# LSGTB.net
KiCad netlist of a schematic drawn in EAGLE
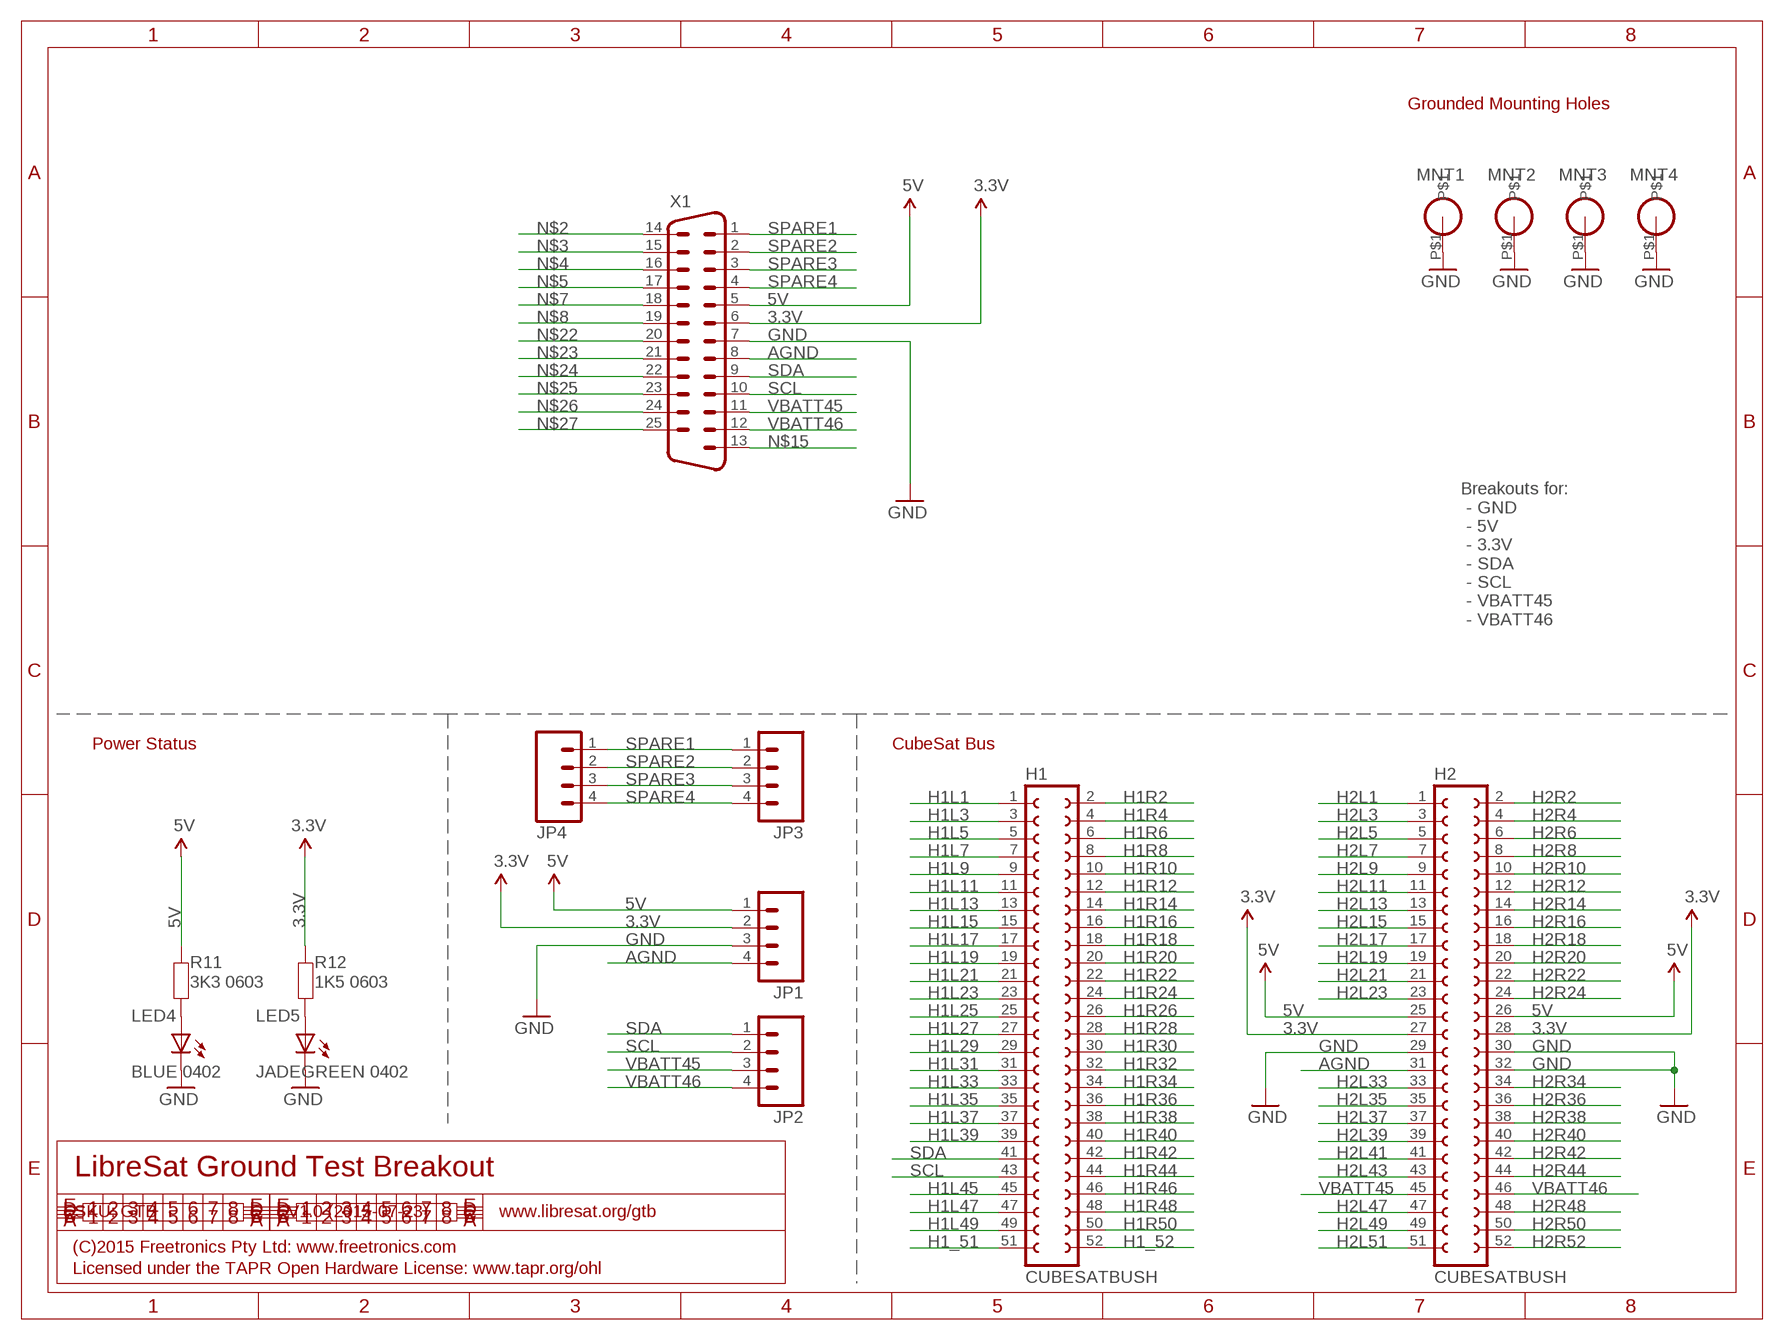
[diagram p0: schematic, sheet 1]

(export (version "E")
  (design (tool "Eeschema 10.0.6"))
  (components
    (comp (ref "H1")
      (value "CUBESATBUSH")
      (footprint "eagle-import:CUBESATBUS")
      (libsource (lib "eagle-import") (part "CUBESATBUSH"))
    )
    (comp (ref "H2")
      (value "CUBESATBUSH")
      (footprint "eagle-import:CUBESATBUS")
      (libsource (lib "eagle-import") (part "CUBESATBUSH"))
    )
    (comp (ref "JP1")
      (value "M04SCREW")
      (footprint "eagle-import:SCREWTERMINAL-3.5MM-4")
      (libsource (lib "eagle-import") (part "M04SCREW"))
    )
    (comp (ref "JP2")
      (value "M04SCREW")
      (footprint "eagle-import:SCREWTERMINAL-3.5MM-4")
      (libsource (lib "eagle-import") (part "M04SCREW"))
    )
    (comp (ref "JP3")
      (value "M04SCREW")
      (footprint "eagle-import:SCREWTERMINAL-3.5MM-4")
      (libsource (lib "eagle-import") (part "M04SCREW"))
    )
    (comp (ref "JP4")
      (value "M04PTH")
      (footprint "eagle-import:1X04")
      (libsource (lib "eagle-import") (part "M04PTH"))
    )
    (comp (ref "LED4")
      (value "BLUE 0402")
      (footprint "eagle-import:LED-0603")
      (libsource (lib "eagle-import") (part "LED0603"))
    )
    (comp (ref "LED5")
      (value "JADEGREEN 0402")
      (footprint "eagle-import:LED-0603")
      (libsource (lib "eagle-import") (part "LED0603"))
    )
    (comp (ref "MNT1")
      (value "HOLE3.2MM")
      (footprint "eagle-import:HOLE32")
      (libsource (lib "eagle-import") (part "HOLE3.2MM"))
    )
    (comp (ref "MNT2")
      (value "HOLE3.2MM")
      (footprint "eagle-import:HOLE32")
      (libsource (lib "eagle-import") (part "HOLE3.2MM"))
    )
    (comp (ref "MNT3")
      (value "HOLE3.2MM")
      (footprint "eagle-import:HOLE32")
      (libsource (lib "eagle-import") (part "HOLE3.2MM"))
    )
    (comp (ref "MNT4")
      (value "HOLE3.2MM")
      (footprint "eagle-import:HOLE32")
      (libsource (lib "eagle-import") (part "HOLE3.2MM"))
    )
    (comp (ref "R11")
      (value "3K3 0603")
      (footprint "eagle-import:0603")
      (libsource (lib "eagle-import") (part "RESISTOR0603"))
    )
    (comp (ref "R12")
      (value "1K5 0603")
      (footprint "eagle-import:0603")
      (libsource (lib "eagle-import") (part "RESISTOR0603"))
    )
    (comp (ref "X1")
      (value "DB25HP")
      (footprint "eagle-import:M25HP")
      (libsource (lib "eagle-import") (part "DB25HP"))
    )
  )
  (nets
    (net (code "1") (name "/AGND") (class "Default")
      (node (ref "H2") (pin "31") (pinfunction "31_31") (pintype "passive"))
      (node (ref "JP1") (pin "4") (pinfunction "4_4") (pintype "passive"))
      (node (ref "X1") (pin "8") (pinfunction "8_8") (pintype "passive"))
    )
    (net (code "2") (name "/H1L1") (class "Default")
      (node (ref "H1") (pin "1") (pinfunction "1_1") (pintype "passive"))
    )
    (net (code "3") (name "/H1L3") (class "Default")
      (node (ref "H1") (pin "3") (pinfunction "3_3") (pintype "passive"))
    )
    (net (code "4") (name "/H1L5") (class "Default")
      (node (ref "H1") (pin "5") (pinfunction "5_5") (pintype "passive"))
    )
    (net (code "5") (name "/H1L7") (class "Default")
      (node (ref "H1") (pin "7") (pinfunction "7_7") (pintype "passive"))
    )
    (net (code "6") (name "/H1L9") (class "Default")
      (node (ref "H1") (pin "9") (pinfunction "9_9") (pintype "passive"))
    )
    (net (code "7") (name "/H1L11") (class "Default")
      (node (ref "H1") (pin "11") (pinfunction "11_11") (pintype "passive"))
    )
    (net (code "8") (name "/H1L13") (class "Default")
      (node (ref "H1") (pin "13") (pinfunction "13_13") (pintype "passive"))
    )
    (net (code "9") (name "/H1L15") (class "Default")
      (node (ref "H1") (pin "15") (pinfunction "15_15") (pintype "passive"))
    )
    (net (code "10") (name "/H1L17") (class "Default")
      (node (ref "H1") (pin "17") (pinfunction "17_17") (pintype "passive"))
    )
    (net (code "11") (name "/H1L19") (class "Default")
      (node (ref "H1") (pin "19") (pinfunction "19_19") (pintype "passive"))
    )
    (net (code "12") (name "/H1L21") (class "Default")
      (node (ref "H1") (pin "21") (pinfunction "21_21") (pintype "passive"))
    )
    (net (code "13") (name "/H1L23") (class "Default")
      (node (ref "H1") (pin "23") (pinfunction "23_23") (pintype "passive"))
    )
    (net (code "14") (name "/H1L25") (class "Default")
      (node (ref "H1") (pin "25") (pinfunction "25_25") (pintype "passive"))
    )
    (net (code "15") (name "/H1L27") (class "Default")
      (node (ref "H1") (pin "27") (pinfunction "27_27") (pintype "passive"))
    )
    (net (code "16") (name "/H1L29") (class "Default")
      (node (ref "H1") (pin "29") (pinfunction "29_29") (pintype "passive"))
    )
    (net (code "17") (name "/H1L31") (class "Default")
      (node (ref "H1") (pin "31") (pinfunction "31_31") (pintype "passive"))
    )
    (net (code "18") (name "/H1L33") (class "Default")
      (node (ref "H1") (pin "33") (pinfunction "33_33") (pintype "passive"))
    )
    (net (code "19") (name "/H1L35") (class "Default")
      (node (ref "H1") (pin "35") (pinfunction "35_35") (pintype "passive"))
    )
    (net (code "20") (name "/H1L37") (class "Default")
      (node (ref "H1") (pin "37") (pinfunction "37_37") (pintype "passive"))
    )
    (net (code "21") (name "/H1L39") (class "Default")
      (node (ref "H1") (pin "39") (pinfunction "39_39") (pintype "passive"))
    )
    (net (code "22") (name "/H1L45") (class "Default")
      (node (ref "H1") (pin "45") (pinfunction "45_45") (pintype "passive"))
    )
    (net (code "23") (name "/H1L47") (class "Default")
      (node (ref "H1") (pin "47") (pinfunction "47_47") (pintype "passive"))
    )
    (net (code "24") (name "/H1L49") (class "Default")
      (node (ref "H1") (pin "49") (pinfunction "49_49") (pintype "passive"))
    )
    (net (code "25") (name "/H1R2") (class "Default")
      (node (ref "H1") (pin "2") (pinfunction "2_2") (pintype "passive"))
    )
    (net (code "26") (name "/H1R4") (class "Default")
      (node (ref "H1") (pin "4") (pinfunction "4_4") (pintype "passive"))
    )
    (net (code "27") (name "/H1R6") (class "Default")
      (node (ref "H1") (pin "6") (pinfunction "6_6") (pintype "passive"))
    )
    (net (code "28") (name "/H1R8") (class "Default")
      (node (ref "H1") (pin "8") (pinfunction "8_8") (pintype "passive"))
    )
    (net (code "29") (name "/H1R10") (class "Default")
      (node (ref "H1") (pin "10") (pinfunction "10_10") (pintype "passive"))
    )
    (net (code "30") (name "/H1R12") (class "Default")
      (node (ref "H1") (pin "12") (pinfunction "12_12") (pintype "passive"))
    )
    (net (code "31") (name "/H1R14") (class "Default")
      (node (ref "H1") (pin "14") (pinfunction "14_14") (pintype "passive"))
    )
    (net (code "32") (name "/H1R16") (class "Default")
      (node (ref "H1") (pin "16") (pinfunction "16_16") (pintype "passive"))
    )
    (net (code "33") (name "/H1R18") (class "Default")
      (node (ref "H1") (pin "18") (pinfunction "18_18") (pintype "passive"))
    )
    (net (code "34") (name "/H1R20") (class "Default")
      (node (ref "H1") (pin "20") (pinfunction "20_20") (pintype "passive"))
    )
    (net (code "35") (name "/H1R22") (class "Default")
      (node (ref "H1") (pin "22") (pinfunction "22_22") (pintype "passive"))
    )
    (net (code "36") (name "/H1R24") (class "Default")
      (node (ref "H1") (pin "24") (pinfunction "24_24") (pintype "passive"))
    )
    (net (code "37") (name "/H1R26") (class "Default")
      (node (ref "H1") (pin "26") (pinfunction "26_26") (pintype "passive"))
    )
    (net (code "38") (name "/H1R28") (class "Default")
      (node (ref "H1") (pin "28") (pinfunction "28_28") (pintype "passive"))
    )
    (net (code "39") (name "/H1R30") (class "Default")
      (node (ref "H1") (pin "30") (pinfunction "30_30") (pintype "passive"))
    )
    (net (code "40") (name "/H1R32") (class "Default")
      (node (ref "H1") (pin "32") (pinfunction "32_32") (pintype "passive"))
    )
    (net (code "41") (name "/H1R34") (class "Default")
      (node (ref "H1") (pin "34") (pinfunction "34_34") (pintype "passive"))
    )
    (net (code "42") (name "/H1R36") (class "Default")
      (node (ref "H1") (pin "36") (pinfunction "36_36") (pintype "passive"))
    )
    (net (code "43") (name "/H1R38") (class "Default")
      (node (ref "H1") (pin "38") (pinfunction "38_38") (pintype "passive"))
    )
    (net (code "44") (name "/H1R40") (class "Default")
      (node (ref "H1") (pin "40") (pinfunction "40_40") (pintype "passive"))
    )
    (net (code "45") (name "/H1R42") (class "Default")
      (node (ref "H1") (pin "42") (pinfunction "42_42") (pintype "passive"))
    )
    (net (code "46") (name "/H1R44") (class "Default")
      (node (ref "H1") (pin "44") (pinfunction "44_44") (pintype "passive"))
    )
    (net (code "47") (name "/H1R46") (class "Default")
      (node (ref "H1") (pin "46") (pinfunction "46_46") (pintype "passive"))
    )
    (net (code "48") (name "/H1R48") (class "Default")
      (node (ref "H1") (pin "48") (pinfunction "48_48") (pintype "passive"))
    )
    (net (code "49") (name "/H1R50") (class "Default")
      (node (ref "H1") (pin "50") (pinfunction "50_50") (pintype "passive"))
    )
    (net (code "50") (name "/H1_51") (class "Default")
      (node (ref "H1") (pin "51") (pinfunction "51_51") (pintype "passive"))
    )
    (net (code "51") (name "/H1_52") (class "Default")
      (node (ref "H1") (pin "52") (pinfunction "52_52") (pintype "passive"))
    )
    (net (code "52") (name "/H2L1") (class "Default")
      (node (ref "H2") (pin "1") (pinfunction "1_1") (pintype "passive"))
    )
    (net (code "53") (name "/H2L3") (class "Default")
      (node (ref "H2") (pin "3") (pinfunction "3_3") (pintype "passive"))
    )
    (net (code "54") (name "/H2L5") (class "Default")
      (node (ref "H2") (pin "5") (pinfunction "5_5") (pintype "passive"))
    )
    (net (code "55") (name "/H2L7") (class "Default")
      (node (ref "H2") (pin "7") (pinfunction "7_7") (pintype "passive"))
    )
    (net (code "56") (name "/H2L9") (class "Default")
      (node (ref "H2") (pin "9") (pinfunction "9_9") (pintype "passive"))
    )
    (net (code "57") (name "/H2L11") (class "Default")
      (node (ref "H2") (pin "11") (pinfunction "11_11") (pintype "passive"))
    )
    (net (code "58") (name "/H2L13") (class "Default")
      (node (ref "H2") (pin "13") (pinfunction "13_13") (pintype "passive"))
    )
    (net (code "59") (name "/H2L15") (class "Default")
      (node (ref "H2") (pin "15") (pinfunction "15_15") (pintype "passive"))
    )
    (net (code "60") (name "/H2L17") (class "Default")
      (node (ref "H2") (pin "17") (pinfunction "17_17") (pintype "passive"))
    )
    (net (code "61") (name "/H2L19") (class "Default")
      (node (ref "H2") (pin "19") (pinfunction "19_19") (pintype "passive"))
    )
    (net (code "62") (name "/H2L21") (class "Default")
      (node (ref "H2") (pin "21") (pinfunction "21_21") (pintype "passive"))
    )
    (net (code "63") (name "/H2L23") (class "Default")
      (node (ref "H2") (pin "23") (pinfunction "23_23") (pintype "passive"))
    )
    (net (code "64") (name "/H2L33") (class "Default")
      (node (ref "H2") (pin "33") (pinfunction "33_33") (pintype "passive"))
    )
    (net (code "65") (name "/H2L35") (class "Default")
      (node (ref "H2") (pin "35") (pinfunction "35_35") (pintype "passive"))
    )
    (net (code "66") (name "/H2L37") (class "Default")
      (node (ref "H2") (pin "37") (pinfunction "37_37") (pintype "passive"))
    )
    (net (code "67") (name "/H2L39") (class "Default")
      (node (ref "H2") (pin "39") (pinfunction "39_39") (pintype "passive"))
    )
    (net (code "68") (name "/H2L41") (class "Default")
      (node (ref "H2") (pin "41") (pinfunction "41_41") (pintype "passive"))
    )
    (net (code "69") (name "/H2L43") (class "Default")
      (node (ref "H2") (pin "43") (pinfunction "43_43") (pintype "passive"))
    )
    (net (code "70") (name "/H2L47") (class "Default")
      (node (ref "H2") (pin "47") (pinfunction "47_47") (pintype "passive"))
    )
    (net (code "71") (name "/H2L49") (class "Default")
      (node (ref "H2") (pin "49") (pinfunction "49_49") (pintype "passive"))
    )
    (net (code "72") (name "/H2L51") (class "Default")
      (node (ref "H2") (pin "51") (pinfunction "51_51") (pintype "passive"))
    )
    (net (code "73") (name "/H2R2") (class "Default")
      (node (ref "H2") (pin "2") (pinfunction "2_2") (pintype "passive"))
    )
    (net (code "74") (name "/H2R4") (class "Default")
      (node (ref "H2") (pin "4") (pinfunction "4_4") (pintype "passive"))
    )
    (net (code "75") (name "/H2R6") (class "Default")
      (node (ref "H2") (pin "6") (pinfunction "6_6") (pintype "passive"))
    )
    (net (code "76") (name "/H2R8") (class "Default")
      (node (ref "H2") (pin "8") (pinfunction "8_8") (pintype "passive"))
    )
    (net (code "77") (name "/H2R10") (class "Default")
      (node (ref "H2") (pin "10") (pinfunction "10_10") (pintype "passive"))
    )
    (net (code "78") (name "/H2R12") (class "Default")
      (node (ref "H2") (pin "12") (pinfunction "12_12") (pintype "passive"))
    )
    (net (code "79") (name "/H2R14") (class "Default")
      (node (ref "H2") (pin "14") (pinfunction "14_14") (pintype "passive"))
    )
    (net (code "80") (name "/H2R16") (class "Default")
      (node (ref "H2") (pin "16") (pinfunction "16_16") (pintype "passive"))
    )
    (net (code "81") (name "/H2R18") (class "Default")
      (node (ref "H2") (pin "18") (pinfunction "18_18") (pintype "passive"))
    )
    (net (code "82") (name "/H2R20") (class "Default")
      (node (ref "H2") (pin "20") (pinfunction "20_20") (pintype "passive"))
    )
    (net (code "83") (name "/H2R22") (class "Default")
      (node (ref "H2") (pin "22") (pinfunction "22_22") (pintype "passive"))
    )
    (net (code "84") (name "/H2R24") (class "Default")
      (node (ref "H2") (pin "24") (pinfunction "24_24") (pintype "passive"))
    )
    (net (code "85") (name "/H2R34") (class "Default")
      (node (ref "H2") (pin "34") (pinfunction "34_34") (pintype "passive"))
    )
    (net (code "86") (name "/H2R36") (class "Default")
      (node (ref "H2") (pin "36") (pinfunction "36_36") (pintype "passive"))
    )
    (net (code "87") (name "/H2R38") (class "Default")
      (node (ref "H2") (pin "38") (pinfunction "38_38") (pintype "passive"))
    )
    (net (code "88") (name "/H2R40") (class "Default")
      (node (ref "H2") (pin "40") (pinfunction "40_40") (pintype "passive"))
    )
    (net (code "89") (name "/H2R42") (class "Default")
      (node (ref "H2") (pin "42") (pinfunction "42_42") (pintype "passive"))
    )
    (net (code "90") (name "/H2R44") (class "Default")
      (node (ref "H2") (pin "44") (pinfunction "44_44") (pintype "passive"))
    )
    (net (code "91") (name "/H2R48") (class "Default")
      (node (ref "H2") (pin "48") (pinfunction "48_48") (pintype "passive"))
    )
    (net (code "92") (name "/H2R50") (class "Default")
      (node (ref "H2") (pin "50") (pinfunction "50_50") (pintype "passive"))
    )
    (net (code "93") (name "/H2R52") (class "Default")
      (node (ref "H2") (pin "52") (pinfunction "52_52") (pintype "passive"))
    )
    (net (code "94") (name "/N$2") (class "Default")
      (node (ref "X1") (pin "14") (pinfunction "14_14") (pintype "passive"))
    )
    (net (code "95") (name "/N$3") (class "Default")
      (node (ref "X1") (pin "15") (pinfunction "15_15") (pintype "passive"))
    )
    (net (code "96") (name "/N$4") (class "Default")
      (node (ref "X1") (pin "16") (pinfunction "16_16") (pintype "passive"))
    )
    (net (code "97") (name "/N$5") (class "Default")
      (node (ref "X1") (pin "17") (pinfunction "17_17") (pintype "passive"))
    )
    (net (code "98") (name "/N$7") (class "Default")
      (node (ref "X1") (pin "18") (pinfunction "18_18") (pintype "passive"))
    )
    (net (code "99") (name "/N$8") (class "Default")
      (node (ref "X1") (pin "19") (pinfunction "19_19") (pintype "passive"))
    )
    (net (code "100") (name "/N$15") (class "Default")
      (node (ref "X1") (pin "13") (pinfunction "13_13") (pintype "passive"))
    )
    (net (code "101") (name "/N$22") (class "Default")
      (node (ref "X1") (pin "20") (pinfunction "20_20") (pintype "passive"))
    )
    (net (code "102") (name "/N$23") (class "Default")
      (node (ref "X1") (pin "21") (pinfunction "21_21") (pintype "passive"))
    )
    (net (code "103") (name "/N$24") (class "Default")
      (node (ref "X1") (pin "22") (pinfunction "22_22") (pintype "passive"))
    )
    (net (code "104") (name "/N$25") (class "Default")
      (node (ref "X1") (pin "23") (pinfunction "23_23") (pintype "passive"))
    )
    (net (code "105") (name "/N$26") (class "Default")
      (node (ref "X1") (pin "24") (pinfunction "24_24") (pintype "passive"))
    )
    (net (code "106") (name "/N$27") (class "Default")
      (node (ref "X1") (pin "25") (pinfunction "25_25") (pintype "passive"))
    )
    (net (code "107") (name "/SCL") (class "Default")
      (node (ref "H1") (pin "43") (pinfunction "43_43") (pintype "passive"))
      (node (ref "JP2") (pin "2") (pinfunction "2_2") (pintype "passive"))
      (node (ref "X1") (pin "10") (pinfunction "10_10") (pintype "passive"))
    )
    (net (code "108") (name "/SDA") (class "Default")
      (node (ref "H1") (pin "41") (pinfunction "41_41") (pintype "passive"))
      (node (ref "JP2") (pin "1") (pinfunction "1_1") (pintype "passive"))
      (node (ref "X1") (pin "9") (pinfunction "9_9") (pintype "passive"))
    )
    (net (code "109") (name "/SPARE1") (class "Default")
      (node (ref "JP3") (pin "1") (pinfunction "1_1") (pintype "passive"))
      (node (ref "JP4") (pin "1") (pinfunction "1_1") (pintype "passive"))
      (node (ref "X1") (pin "1") (pinfunction "1_1") (pintype "passive"))
    )
    (net (code "110") (name "/SPARE2") (class "Default")
      (node (ref "JP3") (pin "2") (pinfunction "2_2") (pintype "passive"))
      (node (ref "JP4") (pin "2") (pinfunction "2_2") (pintype "passive"))
      (node (ref "X1") (pin "2") (pinfunction "2_2") (pintype "passive"))
    )
    (net (code "111") (name "/SPARE3") (class "Default")
      (node (ref "JP3") (pin "3") (pinfunction "3_3") (pintype "passive"))
      (node (ref "JP4") (pin "3") (pinfunction "3_3") (pintype "passive"))
      (node (ref "X1") (pin "3") (pinfunction "3_3") (pintype "passive"))
    )
    (net (code "112") (name "/SPARE4") (class "Default")
      (node (ref "JP3") (pin "4") (pinfunction "4_4") (pintype "passive"))
      (node (ref "JP4") (pin "4") (pinfunction "4_4") (pintype "passive"))
      (node (ref "X1") (pin "4") (pinfunction "4_4") (pintype "passive"))
    )
    (net (code "113") (name "/VBATT45") (class "Default")
      (node (ref "H2") (pin "45") (pinfunction "45_45") (pintype "passive"))
      (node (ref "JP2") (pin "3") (pinfunction "3_3") (pintype "passive"))
      (node (ref "X1") (pin "11") (pinfunction "11_11") (pintype "passive"))
    )
    (net (code "114") (name "/VBATT46") (class "Default")
      (node (ref "H2") (pin "46") (pinfunction "46_46") (pintype "passive"))
      (node (ref "JP2") (pin "4") (pinfunction "4_4") (pintype "passive"))
      (node (ref "X1") (pin "12") (pinfunction "12_12") (pintype "passive"))
    )
    (net (code "115") (name "3.3V") (class "Default")
      (node (ref "H2") (pin "27") (pinfunction "27_27") (pintype "passive"))
      (node (ref "H2") (pin "28") (pinfunction "28_28") (pintype "passive"))
      (node (ref "JP1") (pin "2") (pinfunction "2_2") (pintype "passive"))
      (node (ref "R12") (pin "1") (pinfunction "1_1") (pintype "passive"))
      (node (ref "X1") (pin "6") (pinfunction "6_6") (pintype "passive"))
    )
    (net (code "116") (name "5V") (class "Default")
      (node (ref "H2") (pin "25") (pinfunction "25_25") (pintype "passive"))
      (node (ref "H2") (pin "26") (pinfunction "26_26") (pintype "passive"))
      (node (ref "JP1") (pin "1") (pinfunction "1_1") (pintype "passive"))
      (node (ref "R11") (pin "1") (pinfunction "1_1") (pintype "passive"))
      (node (ref "X1") (pin "5") (pinfunction "5_5") (pintype "passive"))
    )
    (net (code "117") (name "GND") (class "Default")
      (node (ref "H2") (pin "29") (pinfunction "29_29") (pintype "passive"))
      (node (ref "H2") (pin "30") (pinfunction "30_30") (pintype "passive"))
      (node (ref "H2") (pin "32") (pinfunction "32_32") (pintype "passive"))
      (node (ref "JP1") (pin "3") (pinfunction "3_3") (pintype "passive"))
      (node (ref "LED4") (pin "C") (pinfunction "C_C") (pintype "passive"))
      (node (ref "LED5") (pin "C") (pinfunction "C_C") (pintype "passive"))
      (node (ref "MNT1") (pin "P$1") (pinfunction "P$1_P$1") (pintype "bidirectional"))
      (node (ref "MNT2") (pin "P$1") (pinfunction "P$1_P$1") (pintype "bidirectional"))
      (node (ref "MNT3") (pin "P$1") (pinfunction "P$1_P$1") (pintype "bidirectional"))
      (node (ref "MNT4") (pin "P$1") (pinfunction "P$1_P$1") (pintype "bidirectional"))
      (node (ref "X1") (pin "7") (pinfunction "7_7") (pintype "passive"))
    )
    (net (code "118") (name "Net-(LED4-PadA)") (class "Default")
      (node (ref "LED4") (pin "A") (pinfunction "A_A") (pintype "passive"))
      (node (ref "R11") (pin "2") (pinfunction "2_2") (pintype "passive"))
    )
    (net (code "119") (name "Net-(LED5-PadA)") (class "Default")
      (node (ref "LED5") (pin "A") (pinfunction "A_A") (pintype "passive"))
      (node (ref "R12") (pin "2") (pinfunction "2_2") (pintype "passive"))
    )
  )
)
